# SWI_1_0.net
KiCad netlist of a schematic drawn in EAGLE
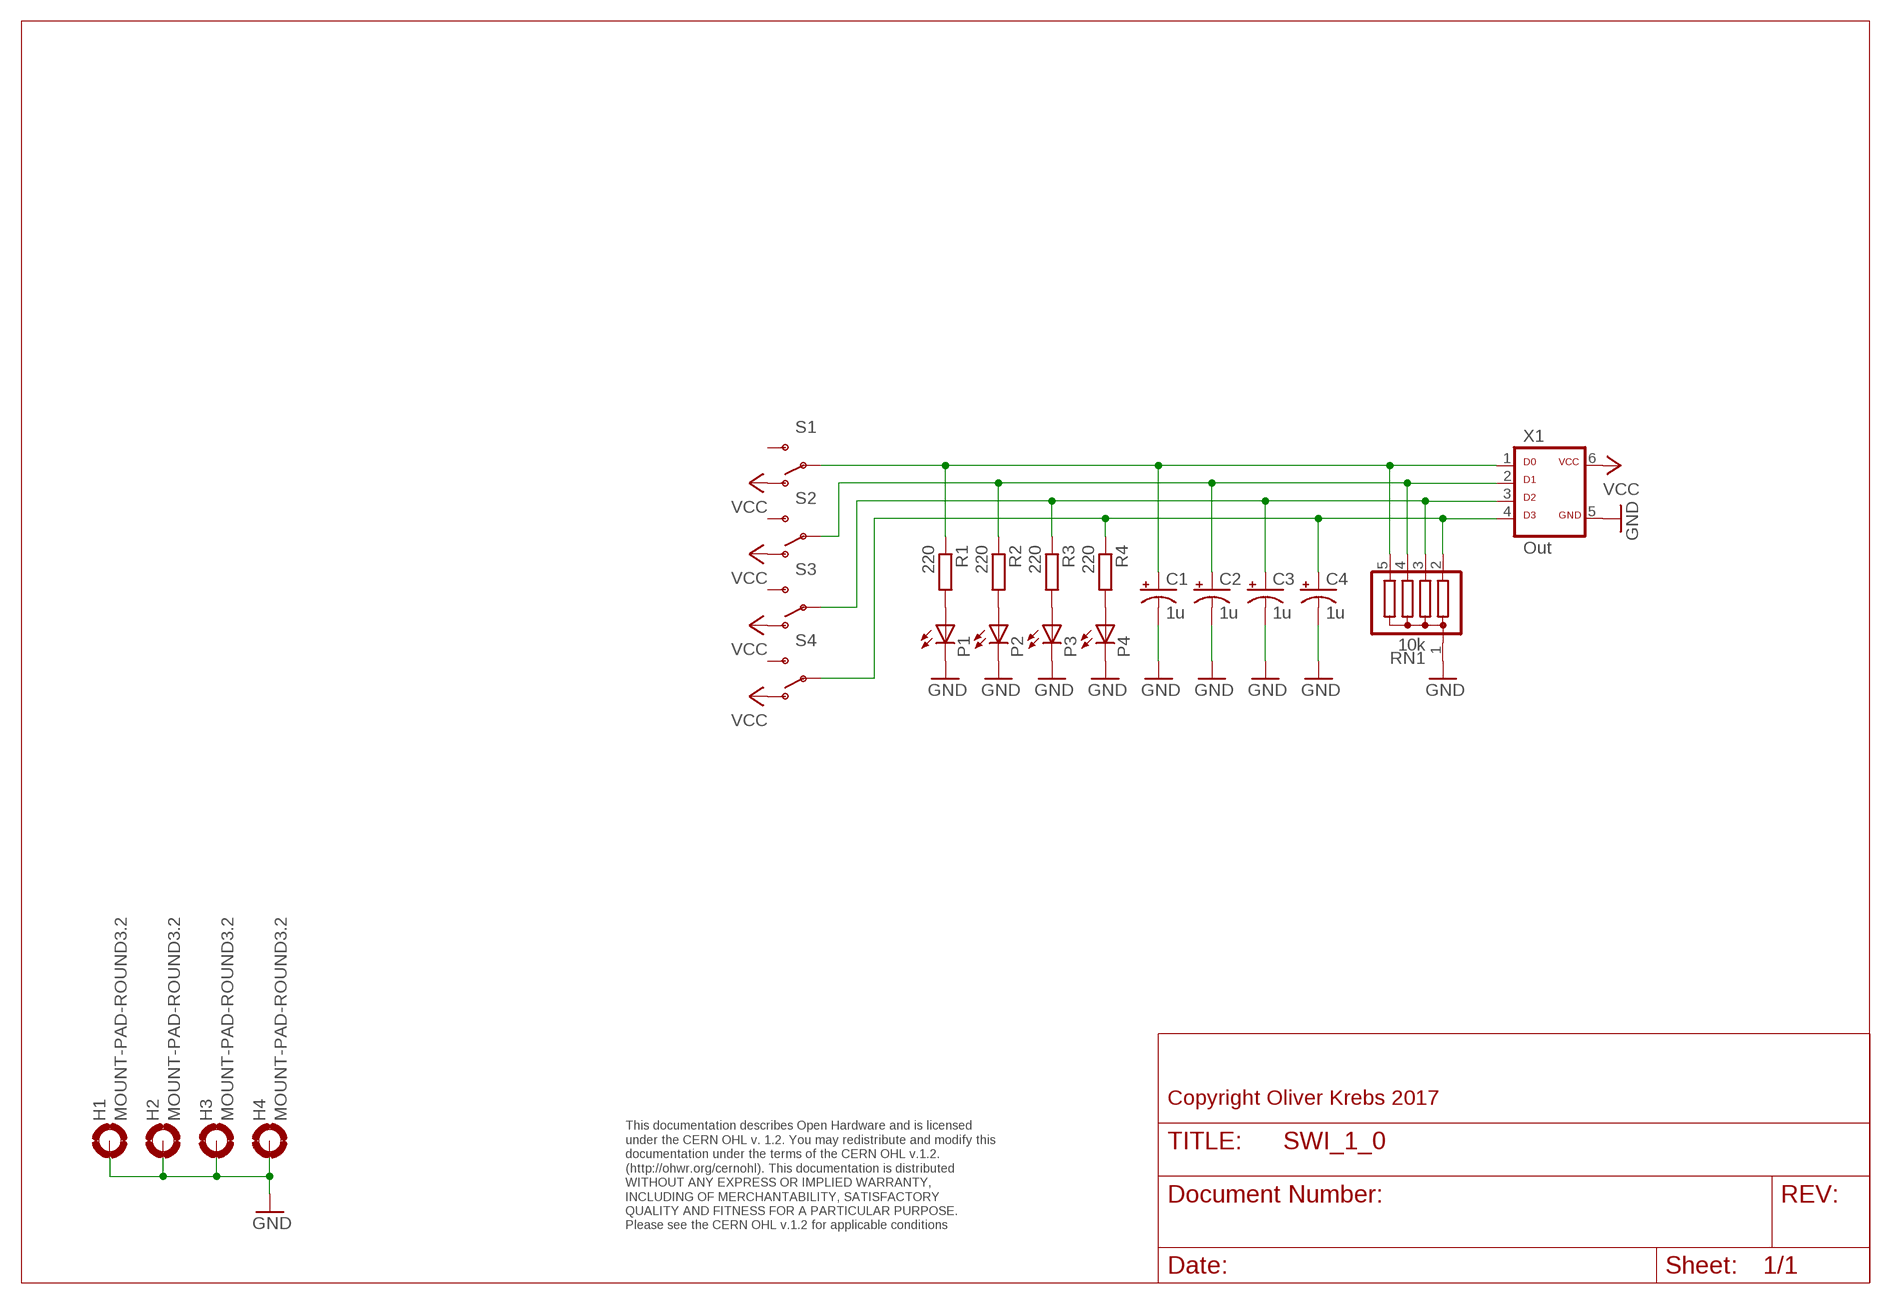
[diagram p0: schematic, sheet 1]

(export (version "E")
  (design (tool "Eeschema 10.0.6"))
  (components
    (comp (ref "C1")
      (value "1u")
      (footprint "eagle-import:CPOL-RADIAL-10UF-25V")
      (libsource (lib "eagle-import") (part "CAP_POLPTH2"))
    )
    (comp (ref "C2")
      (value "1u")
      (footprint "eagle-import:CPOL-RADIAL-10UF-25V")
      (libsource (lib "eagle-import") (part "CAP_POLPTH2"))
    )
    (comp (ref "C3")
      (value "1u")
      (footprint "eagle-import:CPOL-RADIAL-10UF-25V")
      (libsource (lib "eagle-import") (part "CAP_POLPTH2"))
    )
    (comp (ref "C4")
      (value "1u")
      (footprint "eagle-import:CPOL-RADIAL-10UF-25V")
      (libsource (lib "eagle-import") (part "CAP_POLPTH2"))
    )
    (comp (ref "H1")
      (value "MOUNT-PAD-ROUND3.2")
      (footprint "eagle-import:3,2-PAD")
      (libsource (lib "eagle-import") (part "MOUNT-PAD-ROUND3.2"))
    )
    (comp (ref "H2")
      (value "MOUNT-PAD-ROUND3.2")
      (footprint "eagle-import:3,2-PAD")
      (libsource (lib "eagle-import") (part "MOUNT-PAD-ROUND3.2"))
    )
    (comp (ref "H3")
      (value "MOUNT-PAD-ROUND3.2")
      (footprint "eagle-import:3,2-PAD")
      (libsource (lib "eagle-import") (part "MOUNT-PAD-ROUND3.2"))
    )
    (comp (ref "H4")
      (value "MOUNT-PAD-ROUND3.2")
      (footprint "eagle-import:3,2-PAD")
      (libsource (lib "eagle-import") (part "MOUNT-PAD-ROUND3.2"))
    )
    (comp (ref "P1")
      (value "LED3MM")
      (footprint "eagle-import:LED3MM")
      (libsource (lib "eagle-import") (part "LED3MM"))
    )
    (comp (ref "P2")
      (value "LED3MM")
      (footprint "eagle-import:LED3MM")
      (libsource (lib "eagle-import") (part "LED3MM"))
    )
    (comp (ref "P3")
      (value "LED3MM")
      (footprint "eagle-import:LED3MM")
      (libsource (lib "eagle-import") (part "LED3MM"))
    )
    (comp (ref "P4")
      (value "LED3MM")
      (footprint "eagle-import:LED3MM")
      (libsource (lib "eagle-import") (part "LED3MM"))
    )
    (comp (ref "R1")
      (value "220")
      (footprint "eagle-import:0207_10")
      (libsource (lib "eagle-import") (part "R-EU_0207/10"))
    )
    (comp (ref "R2")
      (value "220")
      (footprint "eagle-import:0207_10")
      (libsource (lib "eagle-import") (part "R-EU_0207/10"))
    )
    (comp (ref "R3")
      (value "220")
      (footprint "eagle-import:0207_10")
      (libsource (lib "eagle-import") (part "R-EU_0207/10"))
    )
    (comp (ref "R4")
      (value "220")
      (footprint "eagle-import:0207_10")
      (libsource (lib "eagle-import") (part "R-EU_0207/10"))
    )
    (comp (ref "RN1")
      (value "10k")
      (footprint "eagle-import:SIL5")
      (libsource (lib "eagle-import") (part "G04R"))
    )
    (comp (ref "S1")
      (value "SWITCH-AS500APC")
      (footprint "eagle-import:SWITCH-AS500APC")
      (libsource (lib "eagle-import") (part "SWITCH-AS500APC"))
    )
    (comp (ref "S2")
      (value "SWITCH-AS500APC")
      (footprint "eagle-import:SWITCH-AS500APC")
      (libsource (lib "eagle-import") (part "SWITCH-AS500APC"))
    )
    (comp (ref "S3")
      (value "SWITCH-AS500APC")
      (footprint "eagle-import:SWITCH-AS500APC")
      (libsource (lib "eagle-import") (part "SWITCH-AS500APC"))
    )
    (comp (ref "S4")
      (value "SWITCH-AS500APC")
      (footprint "eagle-import:SWITCH-AS500APC")
      (libsource (lib "eagle-import") (part "SWITCH-AS500APC"))
    )
    (comp (ref "X1")
      (value "Out")
      (footprint "eagle-import:ML-6")
      (libsource (lib "eagle-import") (part "ML6D"))
    )
  )
  (nets
    (net (code "1") (name "GND") (class "Default")
      (node (ref "C1") (pin "2") (pinfunction "-_2") (pintype "passive"))
      (node (ref "C2") (pin "2") (pinfunction "-_2") (pintype "passive"))
      (node (ref "C3") (pin "2") (pinfunction "-_2") (pintype "passive"))
      (node (ref "C4") (pin "2") (pinfunction "-_2") (pintype "passive"))
      (node (ref "H1") (pin "B3,2") (pinfunction "MOUNT_B3,2") (pintype "passive"))
      (node (ref "H2") (pin "B3,2") (pinfunction "MOUNT_B3,2") (pintype "passive"))
      (node (ref "H3") (pin "B3,2") (pinfunction "MOUNT_B3,2") (pintype "passive"))
      (node (ref "H4") (pin "B3,2") (pinfunction "MOUNT_B3,2") (pintype "passive"))
      (node (ref "P1") (pin "K") (pinfunction "C_K") (pintype "passive"))
      (node (ref "P2") (pin "K") (pinfunction "C_K") (pintype "passive"))
      (node (ref "P3") (pin "K") (pinfunction "C_K") (pintype "passive"))
      (node (ref "P4") (pin "K") (pinfunction "C_K") (pintype "passive"))
      (node (ref "RN1") (pin "1") (pinfunction "1_1") (pintype "passive"))
      (node (ref "X1") (pin "5") (pinfunction "5_5") (pintype "passive"))
    )
    (net (code "2") (name "Net-(C1-+)") (class "Default")
      (node (ref "C1") (pin "1") (pinfunction "+_1") (pintype "passive"))
      (node (ref "R1") (pin "1") (pinfunction "1_1") (pintype "passive"))
      (node (ref "RN1") (pin "5") (pinfunction "5_5") (pintype "passive"))
      (node (ref "S1") (pin "P") (pinfunction "P_P") (pintype "passive"))
      (node (ref "X1") (pin "1") (pinfunction "1_1") (pintype "passive"))
    )
    (net (code "3") (name "Net-(C2-+)") (class "Default")
      (node (ref "C2") (pin "1") (pinfunction "+_1") (pintype "passive"))
      (node (ref "R2") (pin "1") (pinfunction "1_1") (pintype "passive"))
      (node (ref "RN1") (pin "4") (pinfunction "4_4") (pintype "passive"))
      (node (ref "S2") (pin "P") (pinfunction "P_P") (pintype "passive"))
      (node (ref "X1") (pin "2") (pinfunction "2_2") (pintype "passive"))
    )
    (net (code "4") (name "Net-(C3-+)") (class "Default")
      (node (ref "C3") (pin "1") (pinfunction "+_1") (pintype "passive"))
      (node (ref "R3") (pin "1") (pinfunction "1_1") (pintype "passive"))
      (node (ref "RN1") (pin "3") (pinfunction "3_3") (pintype "passive"))
      (node (ref "S3") (pin "P") (pinfunction "P_P") (pintype "passive"))
      (node (ref "X1") (pin "3") (pinfunction "3_3") (pintype "passive"))
    )
    (net (code "5") (name "Net-(C4-+)") (class "Default")
      (node (ref "C4") (pin "1") (pinfunction "+_1") (pintype "passive"))
      (node (ref "R4") (pin "1") (pinfunction "1_1") (pintype "passive"))
      (node (ref "RN1") (pin "2") (pinfunction "2_2") (pintype "passive"))
      (node (ref "S4") (pin "P") (pinfunction "P_P") (pintype "passive"))
      (node (ref "X1") (pin "4") (pinfunction "4_4") (pintype "passive"))
    )
    (net (code "6") (name "Net-(P1-PadA)") (class "Default")
      (node (ref "P1") (pin "A") (pinfunction "A_A") (pintype "passive"))
      (node (ref "R1") (pin "2") (pinfunction "2_2") (pintype "passive"))
    )
    (net (code "7") (name "Net-(P2-PadA)") (class "Default")
      (node (ref "P2") (pin "A") (pinfunction "A_A") (pintype "passive"))
      (node (ref "R2") (pin "2") (pinfunction "2_2") (pintype "passive"))
    )
    (net (code "8") (name "Net-(P3-PadA)") (class "Default")
      (node (ref "P3") (pin "A") (pinfunction "A_A") (pintype "passive"))
      (node (ref "R3") (pin "2") (pinfunction "2_2") (pintype "passive"))
    )
    (net (code "9") (name "Net-(P4-PadA)") (class "Default")
      (node (ref "P4") (pin "A") (pinfunction "A_A") (pintype "passive"))
      (node (ref "R4") (pin "2") (pinfunction "2_2") (pintype "passive"))
    )
    (net (code "10") (name "VCC") (class "Default")
      (node (ref "S1") (pin "O") (pinfunction "O_O") (pintype "passive"))
      (node (ref "S2") (pin "O") (pinfunction "O_O") (pintype "passive"))
      (node (ref "S3") (pin "O") (pinfunction "O_O") (pintype "passive"))
      (node (ref "S4") (pin "O") (pinfunction "O_O") (pintype "passive"))
      (node (ref "X1") (pin "6") (pinfunction "6_6") (pintype "passive"))
    )
    (net (code "11") (name "unconnected-(S1-PadS)") (class "Default")
      (node (ref "S1") (pin "S") (pinfunction "S_S") (pintype "passive"))
    )
    (net (code "12") (name "unconnected-(S2-PadS)") (class "Default")
      (node (ref "S2") (pin "S") (pinfunction "S_S") (pintype "passive"))
    )
    (net (code "13") (name "unconnected-(S3-PadS)") (class "Default")
      (node (ref "S3") (pin "S") (pinfunction "S_S") (pintype "passive"))
    )
    (net (code "14") (name "unconnected-(S4-PadS)") (class "Default")
      (node (ref "S4") (pin "S") (pinfunction "S_S") (pintype "passive"))
    )
  )
)
